# giro.net
KiCad netlist of a schematic drawn in Altium Designer
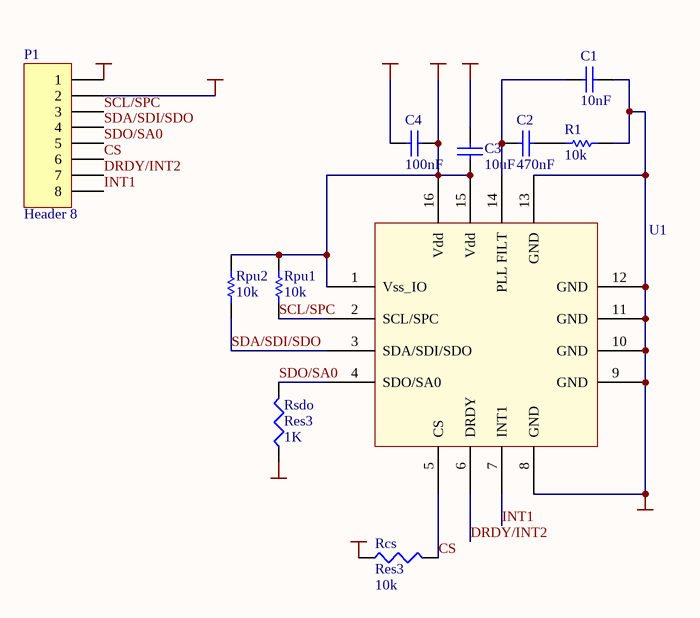
[diagram p0: giro.SchDoc]

(export (version "E")
  (design (tool "Eeschema 10.0.6"))
  (components
    (comp (ref "C1")
      (value "10nF")
      (footprint "L3G4200D:0603")
      (description "Capacitor")
      (fields (field (name "PUBLISHER") "Altium Limited"))
      (libsource (lib "Miscellaneous Devices") (part "Cap"))
    )
    (comp (ref "C2")
      (value "470nF")
      (footprint "L3G4200D:0603")
      (description "Capacitor")
      (fields (field (name "PUBLISHER") "Altium Limited"))
      (libsource (lib "Miscellaneous Devices") (part "Cap"))
    )
    (comp (ref "C3")
      (value "10uF")
      (description "Capacitor")
      (fields (field (name "PUBLISHER") "Altium Limited"))
      (libsource (lib "Miscellaneous Devices") (part "Cap"))
    )
    (comp (ref "C4")
      (value "100nF")
      (description "Capacitor")
      (fields (field (name "PUBLISHER") "Altium Limited"))
      (libsource (lib "Miscellaneous Devices") (part "Cap"))
    )
    (comp (ref "P1")
      (value "Header 8")
      (footprint "HDR1X8")
      (description "Header, 8-Pin")
      (fields (field (name "PUBLISHER") "Altium Limited"))
      (libsource (lib "Miscellaneous Connectors") (part "Header 8"))
    )
    (comp (ref "R1")
      (value "10k")
      (footprint "L3G4200D:0603")
      (description "Semiconductor Resistor")
      (fields (field (name "PUBLISHER") "Altium Limited"))
      (libsource (lib "Miscellaneous Devices") (part "Res Semi"))
    )
    (comp (ref "Rcs")
      (value "Res3")
      (footprint "C1608-0603")
      (description "Resistor")
      (fields (field (name "ALTIUM_VALUE") "10k") (field (name "PUBLISHER") "Altium Limited"))
      (libsource (lib "Miscellaneous Devices") (part "Res3"))
    )
    (comp (ref "Rpu1")
      (value "10k")
      (footprint "L3G4200D:0603")
      (description "Semiconductor Resistor")
      (fields (field (name "PUBLISHER") "Altium Limited"))
      (libsource (lib "Miscellaneous Devices") (part "Res Semi"))
    )
    (comp (ref "Rpu2")
      (value "10k")
      (footprint "L3G4200D:0603")
      (description "Semiconductor Resistor")
      (fields (field (name "PUBLISHER") "Altium Limited"))
      (libsource (lib "Miscellaneous Devices") (part "Res Semi"))
    )
    (comp (ref "Rsdo")
      (value "Res3")
      (footprint "C1608-0603")
      (description "Resistor")
      (fields (field (name "ALTIUM_VALUE") "1K") (field (name "PUBLISHER") "Altium Limited"))
      (libsource (lib "Miscellaneous Devices") (part "Res3"))
    )
    (comp (ref "U1")
      (value "L3G4200D")
      (footprint "L3G4200D")
      (description "Giro 3 axis")
      (libsource (lib "ST_Giro") (part "L3G4200D"))
    )
  )
  (nets
    (net (code "1") (name "/CS") (class "Default")
      (node (ref "P1") (pin "6") (pinfunction "6_6") (pintype "passive"))
      (node (ref "Rcs") (pin "2") (pinfunction "2_2") (pintype "passive"))
      (node (ref "U1") (pin "5") (pinfunction "CS_5") (pintype "passive"))
    )
    (net (code "2") (name "/DRDY{slash}INT2") (class "Default")
      (node (ref "P1") (pin "7") (pinfunction "7_7") (pintype "passive"))
      (node (ref "U1") (pin "6") (pinfunction "DRDY_6") (pintype "passive"))
    )
    (net (code "3") (name "/INT1") (class "Default")
      (node (ref "P1") (pin "8") (pinfunction "8_8") (pintype "passive"))
      (node (ref "U1") (pin "7") (pinfunction "INT1_7") (pintype "passive"))
    )
    (net (code "4") (name "/SCL{slash}SPC") (class "Default")
      (node (ref "P1") (pin "3") (pinfunction "3_3") (pintype "passive"))
      (node (ref "Rpu1") (pin "2") (pinfunction "2_2") (pintype "passive"))
      (node (ref "U1") (pin "2") (pinfunction "SCL/SPC_2") (pintype "passive"))
    )
    (net (code "5") (name "/SDA{slash}SDI{slash}SDO") (class "Default")
      (node (ref "P1") (pin "4") (pinfunction "4_4") (pintype "passive"))
      (node (ref "Rpu2") (pin "2") (pinfunction "2_2") (pintype "passive"))
      (node (ref "U1") (pin "3") (pinfunction "SDA/SDI/SDO_3") (pintype "passive"))
    )
    (net (code "6") (name "/SDO{slash}SA0") (class "Default")
      (node (ref "P1") (pin "5") (pinfunction "5_5") (pintype "passive"))
      (node (ref "Rsdo") (pin "2") (pinfunction "2_2") (pintype "passive"))
      (node (ref "U1") (pin "4") (pinfunction "SDO/SA0_4") (pintype "passive"))
    )
    (net (code "7") (name "GND") (class "Default")
      (node (ref "C1") (pin "1") (pinfunction "1_1") (pintype "passive"))
      (node (ref "C3") (pin "2") (pinfunction "2_2") (pintype "passive"))
      (node (ref "C4") (pin "2") (pinfunction "2_2") (pintype "passive"))
      (node (ref "P1") (pin "1") (pinfunction "1_1") (pintype "passive"))
      (node (ref "R1") (pin "2") (pinfunction "2_2") (pintype "passive"))
      (node (ref "Rsdo") (pin "1") (pinfunction "1_1") (pintype "passive"))
      (node (ref "U1") (pin "10") (pinfunction "GND_10") (pintype "passive"))
      (node (ref "U1") (pin "11") (pinfunction "GND_11") (pintype "passive"))
      (node (ref "U1") (pin "12") (pinfunction "GND_12") (pintype "passive"))
      (node (ref "U1") (pin "13") (pinfunction "GND_13") (pintype "passive"))
      (node (ref "U1") (pin "8") (pinfunction "GND_8") (pintype "passive"))
      (node (ref "U1") (pin "9") (pinfunction "GND_9") (pintype "passive"))
    )
    (net (code "8") (name "Net-(C2-Pad2)") (class "Default")
      (node (ref "C2") (pin "2") (pinfunction "2_2") (pintype "passive"))
      (node (ref "R1") (pin "1") (pinfunction "1_1") (pintype "passive"))
    )
    (net (code "9") (name "Net-(U1-PLL_FILT)") (class "Default")
      (node (ref "C1") (pin "2") (pinfunction "2_2") (pintype "passive"))
      (node (ref "C2") (pin "1") (pinfunction "1_1") (pintype "passive"))
      (node (ref "U1") (pin "14") (pinfunction "PLL_FILT_14") (pintype "passive"))
    )
    (net (code "10") (name "VCC") (class "Default")
      (node (ref "C3") (pin "1") (pinfunction "1_1") (pintype "passive"))
      (node (ref "C4") (pin "1") (pinfunction "1_1") (pintype "passive"))
      (node (ref "P1") (pin "2") (pinfunction "2_2") (pintype "passive"))
      (node (ref "Rcs") (pin "1") (pinfunction "1_1") (pintype "passive"))
      (node (ref "Rpu1") (pin "1") (pinfunction "1_1") (pintype "passive"))
      (node (ref "Rpu2") (pin "1") (pinfunction "1_1") (pintype "passive"))
      (node (ref "U1") (pin "1") (pinfunction "Vss_IO_1") (pintype "passive"))
      (node (ref "U1") (pin "15") (pinfunction "Vdd_15") (pintype "passive"))
      (node (ref "U1") (pin "16") (pinfunction "Vdd_16") (pintype "passive"))
    )
  )
)
